# schematic.net
KiCad netlist of a schematic drawn in Altium Designer
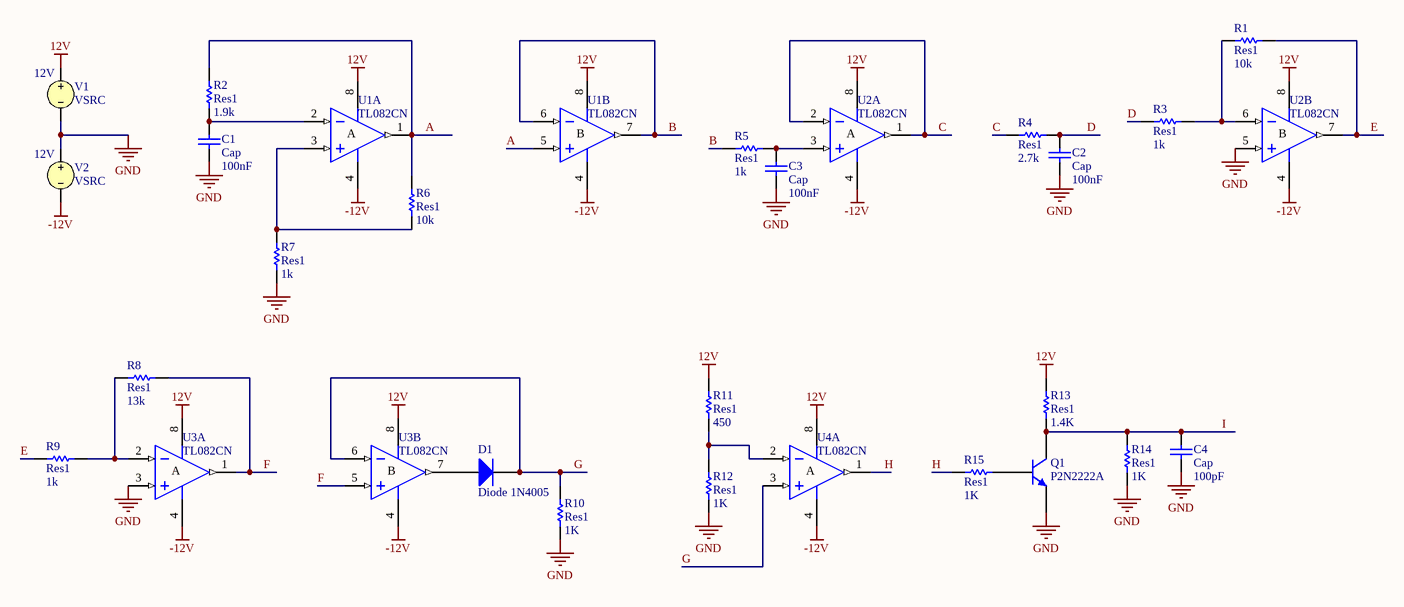
[diagram p0: schematic.SchDoc]

(export (version "E")
  (design (tool "Eeschema 10.0.6"))
  (components
    (comp (ref "C1")
      (value "Cap")
      (footprint "RAD-0.3")
      (description "Capacitor")
      (fields (field (name "ALTIUM_VALUE") "100nF") (field (name "PUBLISHER") "Altium Limited"))
      (libsource (lib "Miscellaneous Devices") (part "Cap"))
    )
    (comp (ref "C2")
      (value "Cap")
      (footprint "RAD-0.3")
      (description "Capacitor")
      (fields (field (name "ALTIUM_VALUE") "100nF") (field (name "PUBLISHER") "Altium Limited"))
      (libsource (lib "Miscellaneous Devices") (part "Cap"))
    )
    (comp (ref "C3")
      (value "Cap")
      (footprint "RAD-0.3")
      (description "Capacitor")
      (fields (field (name "ALTIUM_VALUE") "100nF") (field (name "PUBLISHER") "Altium Limited"))
      (libsource (lib "Miscellaneous Devices") (part "Cap"))
    )
    (comp (ref "C4")
      (value "Cap")
      (footprint "RAD-0.3")
      (description "Capacitor")
      (fields (field (name "ALTIUM_VALUE") "100pF") (field (name "PUBLISHER") "Altium Limited"))
      (libsource (lib "Miscellaneous Devices") (part "Cap"))
    )
    (comp (ref "D1")
      (value "Diode 1N4005")
      (footprint "DO-41")
      (description "1 Amp General Purpose Rectifier")
      (fields (field (name "PUBLISHER") "Altium Limited"))
      (libsource (lib "Miscellaneous Devices") (part "Diode 1N4005"))
    )
    (comp (ref "Q1")
      (value "P2N2222A")
      (footprint "29-04")
      (description "Amplifier Transistor NPN Silicon")
      (fields (field (name "PUBLISHER") "Altium Limited"))
      (libsource (lib "Motorola Discrete BJT") (part "P2N2222A"))
    )
    (comp (ref "R1")
      (value "Res1")
      (footprint "AXIAL-0.3")
      (description "Resistor")
      (fields (field (name "ALTIUM_VALUE") "10k") (field (name "PUBLISHER") "Altium Limited"))
      (libsource (lib "Miscellaneous Devices") (part "Res1"))
    )
    (comp (ref "R2")
      (value "Res1")
      (footprint "AXIAL-0.3")
      (description "Resistor")
      (fields (field (name "ALTIUM_VALUE") "1.9k") (field (name "PUBLISHER") "Altium Limited"))
      (libsource (lib "Miscellaneous Devices") (part "Res1"))
    )
    (comp (ref "R3")
      (value "Res1")
      (footprint "AXIAL-0.3")
      (description "Resistor")
      (fields (field (name "ALTIUM_VALUE") "1k") (field (name "PUBLISHER") "Altium Limited"))
      (libsource (lib "Miscellaneous Devices") (part "Res1"))
    )
    (comp (ref "R4")
      (value "Res1")
      (footprint "AXIAL-0.3")
      (description "Resistor")
      (fields (field (name "ALTIUM_VALUE") "2.7k") (field (name "PUBLISHER") "Altium Limited"))
      (libsource (lib "Miscellaneous Devices") (part "Res1"))
    )
    (comp (ref "R5")
      (value "Res1")
      (footprint "AXIAL-0.3")
      (description "Resistor")
      (fields (field (name "ALTIUM_VALUE") "1k") (field (name "PUBLISHER") "Altium Limited"))
      (libsource (lib "Miscellaneous Devices") (part "Res1"))
    )
    (comp (ref "R6")
      (value "Res1")
      (footprint "AXIAL-0.3")
      (description "Resistor")
      (fields (field (name "ALTIUM_VALUE") "10k") (field (name "PUBLISHER") "Altium Limited"))
      (libsource (lib "Miscellaneous Devices") (part "Res1"))
    )
    (comp (ref "R7")
      (value "Res1")
      (footprint "AXIAL-0.3")
      (description "Resistor")
      (fields (field (name "ALTIUM_VALUE") "1k") (field (name "PUBLISHER") "Altium Limited"))
      (libsource (lib "Miscellaneous Devices") (part "Res1"))
    )
    (comp (ref "R8")
      (value "Res1")
      (footprint "AXIAL-0.3")
      (description "Resistor")
      (fields (field (name "ALTIUM_VALUE") "13k") (field (name "PUBLISHER") "Altium Limited"))
      (libsource (lib "Miscellaneous Devices") (part "Res1"))
    )
    (comp (ref "R9")
      (value "Res1")
      (footprint "AXIAL-0.3")
      (description "Resistor")
      (fields (field (name "ALTIUM_VALUE") "1k") (field (name "PUBLISHER") "Altium Limited"))
      (libsource (lib "Miscellaneous Devices") (part "Res1"))
    )
    (comp (ref "R10")
      (value "Res1")
      (footprint "AXIAL-0.3")
      (description "Resistor")
      (fields (field (name "ALTIUM_VALUE") "1K") (field (name "PUBLISHER") "Altium Limited"))
      (libsource (lib "Miscellaneous Devices") (part "Res1"))
    )
    (comp (ref "R11")
      (value "Res1")
      (footprint "AXIAL-0.3")
      (description "Resistor")
      (fields (field (name "ALTIUM_VALUE") "450") (field (name "PUBLISHER") "Altium Limited"))
      (libsource (lib "Miscellaneous Devices") (part "Res1"))
    )
    (comp (ref "R12")
      (value "Res1")
      (footprint "AXIAL-0.3")
      (description "Resistor")
      (fields (field (name "ALTIUM_VALUE") "1K") (field (name "PUBLISHER") "Altium Limited"))
      (libsource (lib "Miscellaneous Devices") (part "Res1"))
    )
    (comp (ref "R13")
      (value "Res1")
      (footprint "AXIAL-0.3")
      (description "Resistor")
      (fields (field (name "ALTIUM_VALUE") "1.4K") (field (name "PUBLISHER") "Altium Limited"))
      (libsource (lib "Miscellaneous Devices") (part "Res1"))
    )
    (comp (ref "R14")
      (value "Res1")
      (footprint "AXIAL-0.3")
      (description "Resistor")
      (fields (field (name "ALTIUM_VALUE") "1K") (field (name "PUBLISHER") "Altium Limited"))
      (libsource (lib "Miscellaneous Devices") (part "Res1"))
    )
    (comp (ref "R15")
      (value "Res1")
      (footprint "AXIAL-0.3")
      (description "Resistor")
      (fields (field (name "ALTIUM_VALUE") "1K") (field (name "PUBLISHER") "Altium Limited"))
      (libsource (lib "Miscellaneous Devices") (part "Res1"))
    )
    (comp (ref "U1")
      (value "TL082CN")
      (footprint "DIP8")
      (description "General-Purpose J-FET Dual Operational Amplifier")
      (fields (field (name "PUBLISHER") "Altium Limited"))
      (libsource (lib "ST Operational Amplifier") (part "TL082CN"))
    )
    (comp (ref "U2")
      (value "TL082CN")
      (footprint "DIP8")
      (description "General-Purpose J-FET Dual Operational Amplifier")
      (fields (field (name "PUBLISHER") "Altium Limited"))
      (libsource (lib "ST Operational Amplifier") (part "TL082CN"))
    )
    (comp (ref "U3")
      (value "TL082CN")
      (footprint "DIP8")
      (description "General-Purpose J-FET Dual Operational Amplifier")
      (fields (field (name "PUBLISHER") "Altium Limited"))
      (libsource (lib "ST Operational Amplifier") (part "TL082CN"))
    )
    (comp (ref "U4")
      (value "TL082CN")
      (footprint "DIP8")
      (description "General-Purpose J-FET Dual Operational Amplifier")
      (fields (field (name "PUBLISHER") "Altium Limited"))
      (libsource (lib "ST Operational Amplifier") (part "TL082CN"))
    )
    (comp (ref "V1")
      (value "VSRC")
      (description "Voltage Source")
      (fields (field (name "ALTIUM_VALUE") "12V") (field (name "PUBLISHER") "Altium Limited"))
      (libsource (lib "Simulation Sources") (part "VSRC"))
    )
    (comp (ref "V2")
      (value "VSRC")
      (description "Voltage Source")
      (fields (field (name "ALTIUM_VALUE") "12V") (field (name "PUBLISHER") "Altium Limited"))
      (libsource (lib "Simulation Sources") (part "VSRC"))
    )
  )
  (nets
    (net (code "1") (name "-12V") (class "Default")
      (node (ref "U1") (pin "4") (pinfunction "V-_4") (pintype "power_in"))
      (node (ref "U2") (pin "4") (pinfunction "V-_4") (pintype "power_in"))
      (node (ref "U3") (pin "4") (pinfunction "V-_4") (pintype "power_in"))
      (node (ref "U4") (pin "4") (pinfunction "V-_4") (pintype "power_in"))
      (node (ref "V2") (pin "2") (pinfunction "2_2") (pintype "passive"))
    )
    (net (code "2") (name "/A") (class "Default")
      (node (ref "R2") (pin "2") (pinfunction "2_2") (pintype "passive"))
      (node (ref "R6") (pin "2") (pinfunction "2_2") (pintype "passive"))
      (node (ref "U1") (pin "1") (pinfunction "OUT_1") (pintype "output"))
      (node (ref "U1") (pin "5") (pinfunction "IN+_5") (pintype "input"))
    )
    (net (code "3") (name "/B") (class "Default")
      (node (ref "R5") (pin "1") (pinfunction "1_1") (pintype "passive"))
      (node (ref "U1") (pin "6") (pinfunction "IN-_6") (pintype "input"))
      (node (ref "U1") (pin "7") (pinfunction "OUT_7") (pintype "output"))
    )
    (net (code "4") (name "/C") (class "Default")
      (node (ref "R4") (pin "1") (pinfunction "1_1") (pintype "passive"))
      (node (ref "U2") (pin "1") (pinfunction "OUT_1") (pintype "output"))
      (node (ref "U2") (pin "2") (pinfunction "IN-_2") (pintype "input"))
    )
    (net (code "5") (name "/D") (class "Default")
      (node (ref "C2") (pin "2") (pinfunction "2_2") (pintype "passive"))
      (node (ref "R3") (pin "1") (pinfunction "1_1") (pintype "passive"))
      (node (ref "R4") (pin "2") (pinfunction "2_2") (pintype "passive"))
    )
    (net (code "6") (name "/E") (class "Default")
      (node (ref "R1") (pin "2") (pinfunction "2_2") (pintype "passive"))
      (node (ref "R9") (pin "1") (pinfunction "1_1") (pintype "passive"))
      (node (ref "U2") (pin "7") (pinfunction "OUT_7") (pintype "output"))
    )
    (net (code "7") (name "/F") (class "Default")
      (node (ref "R8") (pin "2") (pinfunction "2_2") (pintype "passive"))
      (node (ref "U3") (pin "1") (pinfunction "OUT_1") (pintype "output"))
      (node (ref "U3") (pin "5") (pinfunction "IN+_5") (pintype "input"))
    )
    (net (code "8") (name "/G") (class "Default")
      (node (ref "D1") (pin "2") (pinfunction "K_2") (pintype "passive"))
      (node (ref "R10") (pin "2") (pinfunction "2_2") (pintype "passive"))
      (node (ref "U3") (pin "6") (pinfunction "IN-_6") (pintype "input"))
      (node (ref "U4") (pin "3") (pinfunction "IN+_3") (pintype "input"))
    )
    (net (code "9") (name "/H") (class "Default")
      (node (ref "R15") (pin "2") (pinfunction "2_2") (pintype "passive"))
      (node (ref "U4") (pin "1") (pinfunction "OUT_1") (pintype "output"))
    )
    (net (code "10") (name "/I") (class "Default")
      (node (ref "C4") (pin "2") (pinfunction "2_2") (pintype "passive"))
      (node (ref "Q1") (pin "1") (pinfunction "C_1") (pintype "passive"))
      (node (ref "R13") (pin "1") (pinfunction "1_1") (pintype "passive"))
      (node (ref "R14") (pin "2") (pinfunction "2_2") (pintype "passive"))
    )
    (net (code "11") (name "12V") (class "Default")
      (node (ref "R11") (pin "2") (pinfunction "2_2") (pintype "passive"))
      (node (ref "R13") (pin "2") (pinfunction "2_2") (pintype "passive"))
      (node (ref "U1") (pin "8") (pinfunction "V+_8") (pintype "power_in"))
      (node (ref "U2") (pin "8") (pinfunction "V+_8") (pintype "power_in"))
      (node (ref "U3") (pin "8") (pinfunction "V+_8") (pintype "power_in"))
      (node (ref "U4") (pin "8") (pinfunction "V+_8") (pintype "power_in"))
      (node (ref "V1") (pin "1") (pinfunction "1_1") (pintype "passive"))
    )
    (net (code "12") (name "GND") (class "Default")
      (node (ref "C1") (pin "1") (pinfunction "1_1") (pintype "passive"))
      (node (ref "C2") (pin "1") (pinfunction "1_1") (pintype "passive"))
      (node (ref "C3") (pin "1") (pinfunction "1_1") (pintype "passive"))
      (node (ref "C4") (pin "1") (pinfunction "1_1") (pintype "passive"))
      (node (ref "Q1") (pin "3") (pinfunction "E_3") (pintype "passive"))
      (node (ref "R10") (pin "1") (pinfunction "1_1") (pintype "passive"))
      (node (ref "R12") (pin "1") (pinfunction "1_1") (pintype "passive"))
      (node (ref "R14") (pin "1") (pinfunction "1_1") (pintype "passive"))
      (node (ref "R7") (pin "1") (pinfunction "1_1") (pintype "passive"))
      (node (ref "U2") (pin "5") (pinfunction "IN+_5") (pintype "input"))
      (node (ref "U3") (pin "3") (pinfunction "IN+_3") (pintype "input"))
      (node (ref "V1") (pin "2") (pinfunction "2_2") (pintype "passive"))
      (node (ref "V2") (pin "1") (pinfunction "1_1") (pintype "passive"))
    )
    (net (code "13") (name "Net-(D1-A)") (class "Default")
      (node (ref "D1") (pin "1") (pinfunction "A_1") (pintype "passive"))
      (node (ref "U3") (pin "7") (pinfunction "OUT_7") (pintype "output"))
    )
    (net (code "14") (name "Net-(Q1-B)") (class "Default")
      (node (ref "Q1") (pin "2") (pinfunction "B_2") (pintype "passive"))
      (node (ref "R15") (pin "1") (pinfunction "1_1") (pintype "passive"))
    )
    (net (code "15") (name "Net-(U1A-IN+)") (class "Default")
      (node (ref "R6") (pin "1") (pinfunction "1_1") (pintype "passive"))
      (node (ref "R7") (pin "2") (pinfunction "2_2") (pintype "passive"))
      (node (ref "U1") (pin "3") (pinfunction "IN+_3") (pintype "input"))
    )
    (net (code "16") (name "Net-(U1A-IN-)") (class "Default")
      (node (ref "C1") (pin "2") (pinfunction "2_2") (pintype "passive"))
      (node (ref "R2") (pin "1") (pinfunction "1_1") (pintype "passive"))
      (node (ref "U1") (pin "2") (pinfunction "IN-_2") (pintype "input"))
    )
    (net (code "17") (name "Net-(U2A-IN+)") (class "Default")
      (node (ref "C3") (pin "2") (pinfunction "2_2") (pintype "passive"))
      (node (ref "R5") (pin "2") (pinfunction "2_2") (pintype "passive"))
      (node (ref "U2") (pin "3") (pinfunction "IN+_3") (pintype "input"))
    )
    (net (code "18") (name "Net-(U2B-IN-)") (class "Default")
      (node (ref "R1") (pin "1") (pinfunction "1_1") (pintype "passive"))
      (node (ref "R3") (pin "2") (pinfunction "2_2") (pintype "passive"))
      (node (ref "U2") (pin "6") (pinfunction "IN-_6") (pintype "input"))
    )
    (net (code "19") (name "Net-(U3A-IN-)") (class "Default")
      (node (ref "R8") (pin "1") (pinfunction "1_1") (pintype "passive"))
      (node (ref "R9") (pin "2") (pinfunction "2_2") (pintype "passive"))
      (node (ref "U3") (pin "2") (pinfunction "IN-_2") (pintype "input"))
    )
    (net (code "20") (name "Net-(U4A-IN-)") (class "Default")
      (node (ref "R11") (pin "1") (pinfunction "1_1") (pintype "passive"))
      (node (ref "R12") (pin "2") (pinfunction "2_2") (pintype "passive"))
      (node (ref "U4") (pin "2") (pinfunction "IN-_2") (pintype "input"))
    )
  )
)
